# M900dec.net
KiCad netlist of a schematic drawn in EAGLE
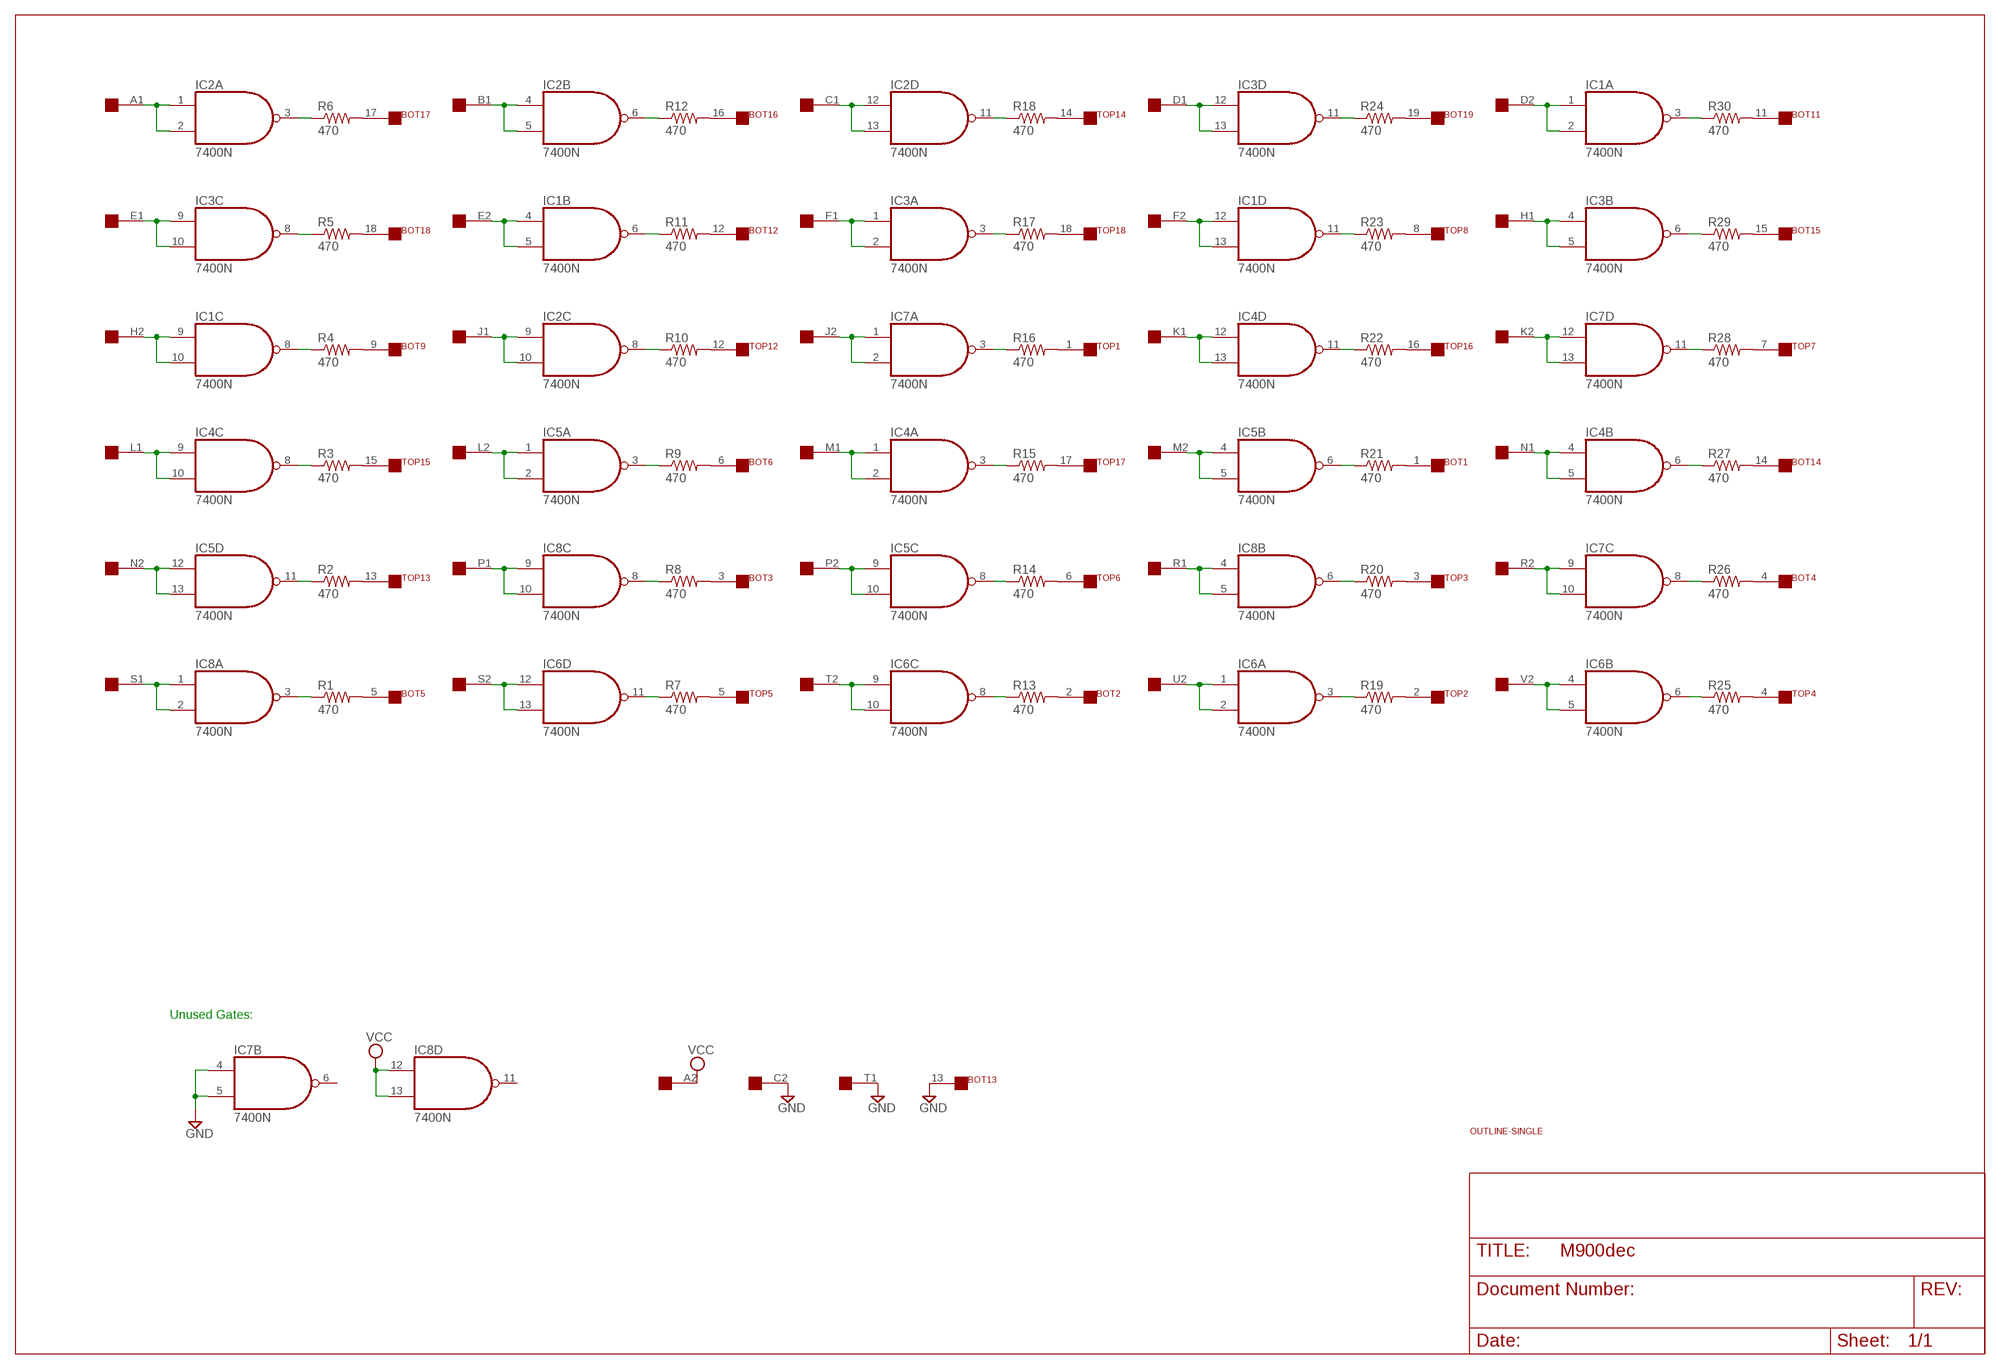
[diagram p0: schematic, sheet 1]

(export (version "E")
  (design (tool "Eeschema 10.0.6"))
  (components
    (comp (ref "BOT")
      (value "FLEX19")
      (footprint "eagle-import:FLEX19")
      (libsource (lib "eagle-import") (part "FLEX19"))
    )
    (comp (ref "EDGE")
      (value "SINGLE")
      (footprint "eagle-import:EDGE-CON2")
      (libsource (lib "eagle-import") (part "SINGLE"))
    )
    (comp (ref "IC1")
      (value "7400N")
      (footprint "eagle-import:DIL14")
      (libsource (lib "eagle-import") (part "7400N"))
    )
    (comp (ref "IC2")
      (value "7400N")
      (footprint "eagle-import:DIL14")
      (libsource (lib "eagle-import") (part "7400N"))
    )
    (comp (ref "IC3")
      (value "7400N")
      (footprint "eagle-import:DIL14")
      (libsource (lib "eagle-import") (part "7400N"))
    )
    (comp (ref "IC4")
      (value "7400N")
      (footprint "eagle-import:DIL14")
      (libsource (lib "eagle-import") (part "7400N"))
    )
    (comp (ref "IC5")
      (value "7400N")
      (footprint "eagle-import:DIL14")
      (libsource (lib "eagle-import") (part "7400N"))
    )
    (comp (ref "IC6")
      (value "7400N")
      (footprint "eagle-import:DIL14")
      (libsource (lib "eagle-import") (part "7400N"))
    )
    (comp (ref "IC7")
      (value "7400N")
      (footprint "eagle-import:DIL14")
      (libsource (lib "eagle-import") (part "7400N"))
    )
    (comp (ref "IC8")
      (value "7400N")
      (footprint "eagle-import:DIL14")
      (libsource (lib "eagle-import") (part "7400N"))
    )
    (comp (ref "R1")
      (value "470")
      (footprint "eagle-import:0207_10")
      (libsource (lib "eagle-import") (part "R-US_0207/10"))
    )
    (comp (ref "R2")
      (value "470")
      (footprint "eagle-import:0207_10")
      (libsource (lib "eagle-import") (part "R-US_0207/10"))
    )
    (comp (ref "R3")
      (value "470")
      (footprint "eagle-import:0207_10")
      (libsource (lib "eagle-import") (part "R-US_0207/10"))
    )
    (comp (ref "R4")
      (value "470")
      (footprint "eagle-import:0207_10")
      (libsource (lib "eagle-import") (part "R-US_0207/10"))
    )
    (comp (ref "R5")
      (value "470")
      (footprint "eagle-import:0207_10")
      (libsource (lib "eagle-import") (part "R-US_0207/10"))
    )
    (comp (ref "R6")
      (value "470")
      (footprint "eagle-import:0207_10")
      (libsource (lib "eagle-import") (part "R-US_0207/10"))
    )
    (comp (ref "R7")
      (value "470")
      (footprint "eagle-import:0207_10")
      (libsource (lib "eagle-import") (part "R-US_0207/10"))
    )
    (comp (ref "R8")
      (value "470")
      (footprint "eagle-import:0207_10")
      (libsource (lib "eagle-import") (part "R-US_0207/10"))
    )
    (comp (ref "R9")
      (value "470")
      (footprint "eagle-import:0207_10")
      (libsource (lib "eagle-import") (part "R-US_0207/10"))
    )
    (comp (ref "R10")
      (value "470")
      (footprint "eagle-import:0207_10")
      (libsource (lib "eagle-import") (part "R-US_0207/10"))
    )
    (comp (ref "R11")
      (value "470")
      (footprint "eagle-import:0207_10")
      (libsource (lib "eagle-import") (part "R-US_0207/10"))
    )
    (comp (ref "R12")
      (value "470")
      (footprint "eagle-import:0207_10")
      (libsource (lib "eagle-import") (part "R-US_0207/10"))
    )
    (comp (ref "R13")
      (value "470")
      (footprint "eagle-import:0207_10")
      (libsource (lib "eagle-import") (part "R-US_0207/10"))
    )
    (comp (ref "R14")
      (value "470")
      (footprint "eagle-import:0207_10")
      (libsource (lib "eagle-import") (part "R-US_0207/10"))
    )
    (comp (ref "R15")
      (value "470")
      (footprint "eagle-import:0207_10")
      (libsource (lib "eagle-import") (part "R-US_0207/10"))
    )
    (comp (ref "R16")
      (value "470")
      (footprint "eagle-import:0207_10")
      (libsource (lib "eagle-import") (part "R-US_0207/10"))
    )
    (comp (ref "R17")
      (value "470")
      (footprint "eagle-import:0207_10")
      (libsource (lib "eagle-import") (part "R-US_0207/10"))
    )
    (comp (ref "R18")
      (value "470")
      (footprint "eagle-import:0207_10")
      (libsource (lib "eagle-import") (part "R-US_0207/10"))
    )
    (comp (ref "R19")
      (value "470")
      (footprint "eagle-import:0207_10")
      (libsource (lib "eagle-import") (part "R-US_0207/10"))
    )
    (comp (ref "R20")
      (value "470")
      (footprint "eagle-import:0207_10")
      (libsource (lib "eagle-import") (part "R-US_0207/10"))
    )
    (comp (ref "R21")
      (value "470")
      (footprint "eagle-import:0207_10")
      (libsource (lib "eagle-import") (part "R-US_0207/10"))
    )
    (comp (ref "R22")
      (value "470")
      (footprint "eagle-import:0207_10")
      (libsource (lib "eagle-import") (part "R-US_0207/10"))
    )
    (comp (ref "R23")
      (value "470")
      (footprint "eagle-import:0207_10")
      (libsource (lib "eagle-import") (part "R-US_0207/10"))
    )
    (comp (ref "R24")
      (value "470")
      (footprint "eagle-import:0207_10")
      (libsource (lib "eagle-import") (part "R-US_0207/10"))
    )
    (comp (ref "R25")
      (value "470")
      (footprint "eagle-import:0207_10")
      (libsource (lib "eagle-import") (part "R-US_0207/10"))
    )
    (comp (ref "R26")
      (value "470")
      (footprint "eagle-import:0207_10")
      (libsource (lib "eagle-import") (part "R-US_0207/10"))
    )
    (comp (ref "R27")
      (value "470")
      (footprint "eagle-import:0207_10")
      (libsource (lib "eagle-import") (part "R-US_0207/10"))
    )
    (comp (ref "R28")
      (value "470")
      (footprint "eagle-import:0207_10")
      (libsource (lib "eagle-import") (part "R-US_0207/10"))
    )
    (comp (ref "R29")
      (value "470")
      (footprint "eagle-import:0207_10")
      (libsource (lib "eagle-import") (part "R-US_0207/10"))
    )
    (comp (ref "R30")
      (value "470")
      (footprint "eagle-import:0207_10")
      (libsource (lib "eagle-import") (part "R-US_0207/10"))
    )
    (comp (ref "TOP")
      (value "FLEX19")
      (footprint "eagle-import:FLEX19")
      (libsource (lib "eagle-import") (part "FLEX19"))
    )
    (comp (ref "U$2")
      (value "OUTLINE-SINGLE")
      (footprint "eagle-import:SINGLE")
      (libsource (lib "eagle-import") (part "OUTLINE-SINGLE"))
    )
  )
  (nets
    (net (code "1") (name "GND") (class "Default")
      (node (ref "BOT") (pin "13") (pinfunction "1_13") (pintype "passive"))
      (node (ref "EDGE") (pin "C2") (pinfunction "1_C2") (pintype "bidirectional"))
      (node (ref "EDGE") (pin "T1") (pinfunction "1_T1") (pintype "bidirectional"))
      (node (ref "IC7") (pin "4") (pinfunction "I0_4") (pintype "input"))
      (node (ref "IC7") (pin "5") (pinfunction "I1_5") (pintype "input"))
    )
    (net (code "2") (name "Net-(BOT-Pad1)") (class "Default")
      (node (ref "BOT") (pin "1") (pinfunction "1_1") (pintype "passive"))
      (node (ref "R21") (pin "2") (pinfunction "2_2") (pintype "passive"))
    )
    (net (code "3") (name "Net-(BOTC-1)") (class "Default")
      (node (ref "BOT") (pin "11") (pinfunction "1_11") (pintype "passive"))
      (node (ref "R30") (pin "2") (pinfunction "2_2") (pintype "passive"))
    )
    (net (code "4") (name "Net-(BOTD-1)") (class "Default")
      (node (ref "BOT") (pin "12") (pinfunction "1_12") (pintype "passive"))
      (node (ref "R11") (pin "2") (pinfunction "2_2") (pintype "passive"))
    )
    (net (code "5") (name "Net-(BOTF-1)") (class "Default")
      (node (ref "BOT") (pin "14") (pinfunction "1_14") (pintype "passive"))
      (node (ref "R27") (pin "2") (pinfunction "2_2") (pintype "passive"))
    )
    (net (code "6") (name "Net-(BOTG-1)") (class "Default")
      (node (ref "BOT") (pin "15") (pinfunction "1_15") (pintype "passive"))
      (node (ref "R29") (pin "2") (pinfunction "2_2") (pintype "passive"))
    )
    (net (code "7") (name "Net-(BOTH-1)") (class "Default")
      (node (ref "BOT") (pin "16") (pinfunction "1_16") (pintype "passive"))
      (node (ref "R12") (pin "2") (pinfunction "2_2") (pintype "passive"))
    )
    (net (code "8") (name "Net-(BOTI-1)") (class "Default")
      (node (ref "BOT") (pin "17") (pinfunction "1_17") (pintype "passive"))
      (node (ref "R6") (pin "2") (pinfunction "2_2") (pintype "passive"))
    )
    (net (code "9") (name "Net-(BOTJ-1)") (class "Default")
      (node (ref "BOT") (pin "18") (pinfunction "1_18") (pintype "passive"))
      (node (ref "R5") (pin "2") (pinfunction "2_2") (pintype "passive"))
    )
    (net (code "10") (name "Net-(BOTK-1)") (class "Default")
      (node (ref "BOT") (pin "19") (pinfunction "1_19") (pintype "passive"))
      (node (ref "R24") (pin "2") (pinfunction "2_2") (pintype "passive"))
    )
    (net (code "11") (name "Net-(BOTL-1)") (class "Default")
      (node (ref "BOT") (pin "2") (pinfunction "1_2") (pintype "passive"))
      (node (ref "R13") (pin "2") (pinfunction "2_2") (pintype "passive"))
    )
    (net (code "12") (name "Net-(BOTM-1)") (class "Default")
      (node (ref "BOT") (pin "3") (pinfunction "1_3") (pintype "passive"))
      (node (ref "R8") (pin "2") (pinfunction "2_2") (pintype "passive"))
    )
    (net (code "13") (name "Net-(BOTN-1)") (class "Default")
      (node (ref "BOT") (pin "4") (pinfunction "1_4") (pintype "passive"))
      (node (ref "R26") (pin "2") (pinfunction "2_2") (pintype "passive"))
    )
    (net (code "14") (name "Net-(BOTO-1)") (class "Default")
      (node (ref "BOT") (pin "5") (pinfunction "1_5") (pintype "passive"))
      (node (ref "R1") (pin "2") (pinfunction "2_2") (pintype "passive"))
    )
    (net (code "15") (name "Net-(BOTP-1)") (class "Default")
      (node (ref "BOT") (pin "6") (pinfunction "1_6") (pintype "passive"))
      (node (ref "R9") (pin "2") (pinfunction "2_2") (pintype "passive"))
    )
    (net (code "16") (name "Net-(BOTS-1)") (class "Default")
      (node (ref "BOT") (pin "9") (pinfunction "1_9") (pintype "passive"))
      (node (ref "R4") (pin "2") (pinfunction "2_2") (pintype "passive"))
    )
    (net (code "17") (name "Net-(EDGEA-1)") (class "Default")
      (node (ref "EDGE") (pin "A1") (pinfunction "1_A1") (pintype "bidirectional"))
      (node (ref "IC2") (pin "1") (pinfunction "I0_1") (pintype "input"))
      (node (ref "IC2") (pin "2") (pinfunction "I1_2") (pintype "input"))
    )
    (net (code "18") (name "Net-(EDGEAA-1)") (class "Default")
      (node (ref "EDGE") (pin "R1") (pinfunction "1_R1") (pintype "bidirectional"))
      (node (ref "IC8") (pin "4") (pinfunction "I0_4") (pintype "input"))
      (node (ref "IC8") (pin "5") (pinfunction "I1_5") (pintype "input"))
    )
    (net (code "19") (name "Net-(EDGEAB-1)") (class "Default")
      (node (ref "EDGE") (pin "R2") (pinfunction "1_R2") (pintype "bidirectional"))
      (node (ref "IC7") (pin "10") (pinfunction "I1_10") (pintype "input"))
      (node (ref "IC7") (pin "9") (pinfunction "I0_9") (pintype "input"))
    )
    (net (code "20") (name "Net-(EDGEAC-1)") (class "Default")
      (node (ref "EDGE") (pin "S1") (pinfunction "1_S1") (pintype "bidirectional"))
      (node (ref "IC8") (pin "1") (pinfunction "I0_1") (pintype "input"))
      (node (ref "IC8") (pin "2") (pinfunction "I1_2") (pintype "input"))
    )
    (net (code "21") (name "Net-(EDGEAD-1)") (class "Default")
      (node (ref "EDGE") (pin "S2") (pinfunction "1_S2") (pintype "bidirectional"))
      (node (ref "IC6") (pin "12") (pinfunction "I0_12") (pintype "input"))
      (node (ref "IC6") (pin "13") (pinfunction "I1_13") (pintype "input"))
    )
    (net (code "22") (name "Net-(EDGEAF-1)") (class "Default")
      (node (ref "EDGE") (pin "T2") (pinfunction "1_T2") (pintype "bidirectional"))
      (node (ref "IC6") (pin "10") (pinfunction "I1_10") (pintype "input"))
      (node (ref "IC6") (pin "9") (pinfunction "I0_9") (pintype "input"))
    )
    (net (code "23") (name "Net-(EDGEAH-1)") (class "Default")
      (node (ref "EDGE") (pin "U2") (pinfunction "1_U2") (pintype "bidirectional"))
      (node (ref "IC6") (pin "1") (pinfunction "I0_1") (pintype "input"))
      (node (ref "IC6") (pin "2") (pinfunction "I1_2") (pintype "input"))
    )
    (net (code "24") (name "Net-(EDGEAJ-1)") (class "Default")
      (node (ref "EDGE") (pin "V2") (pinfunction "1_V2") (pintype "bidirectional"))
      (node (ref "IC6") (pin "4") (pinfunction "I0_4") (pintype "input"))
      (node (ref "IC6") (pin "5") (pinfunction "I1_5") (pintype "input"))
    )
    (net (code "25") (name "Net-(EDGEC-1)") (class "Default")
      (node (ref "EDGE") (pin "B1") (pinfunction "1_B1") (pintype "bidirectional"))
      (node (ref "IC2") (pin "4") (pinfunction "I0_4") (pintype "input"))
      (node (ref "IC2") (pin "5") (pinfunction "I1_5") (pintype "input"))
    )
    (net (code "26") (name "Net-(EDGEE-1)") (class "Default")
      (node (ref "EDGE") (pin "C1") (pinfunction "1_C1") (pintype "bidirectional"))
      (node (ref "IC2") (pin "12") (pinfunction "I0_12") (pintype "input"))
      (node (ref "IC2") (pin "13") (pinfunction "I1_13") (pintype "input"))
    )
    (net (code "27") (name "Net-(EDGEG-1)") (class "Default")
      (node (ref "EDGE") (pin "D1") (pinfunction "1_D1") (pintype "bidirectional"))
      (node (ref "IC3") (pin "12") (pinfunction "I0_12") (pintype "input"))
      (node (ref "IC3") (pin "13") (pinfunction "I1_13") (pintype "input"))
    )
    (net (code "28") (name "Net-(EDGEH-1)") (class "Default")
      (node (ref "EDGE") (pin "D2") (pinfunction "1_D2") (pintype "bidirectional"))
      (node (ref "IC1") (pin "1") (pinfunction "I0_1") (pintype "input"))
      (node (ref "IC1") (pin "2") (pinfunction "I1_2") (pintype "input"))
    )
    (net (code "29") (name "Net-(EDGEI-1)") (class "Default")
      (node (ref "EDGE") (pin "E1") (pinfunction "1_E1") (pintype "bidirectional"))
      (node (ref "IC3") (pin "10") (pinfunction "I1_10") (pintype "input"))
      (node (ref "IC3") (pin "9") (pinfunction "I0_9") (pintype "input"))
    )
    (net (code "30") (name "Net-(EDGEJ-1)") (class "Default")
      (node (ref "EDGE") (pin "E2") (pinfunction "1_E2") (pintype "bidirectional"))
      (node (ref "IC1") (pin "4") (pinfunction "I0_4") (pintype "input"))
      (node (ref "IC1") (pin "5") (pinfunction "I1_5") (pintype "input"))
    )
    (net (code "31") (name "Net-(EDGEK-1)") (class "Default")
      (node (ref "EDGE") (pin "F1") (pinfunction "1_F1") (pintype "bidirectional"))
      (node (ref "IC3") (pin "1") (pinfunction "I0_1") (pintype "input"))
      (node (ref "IC3") (pin "2") (pinfunction "I1_2") (pintype "input"))
    )
    (net (code "32") (name "Net-(EDGEL-1)") (class "Default")
      (node (ref "EDGE") (pin "F2") (pinfunction "1_F2") (pintype "bidirectional"))
      (node (ref "IC1") (pin "12") (pinfunction "I0_12") (pintype "input"))
      (node (ref "IC1") (pin "13") (pinfunction "I1_13") (pintype "input"))
    )
    (net (code "33") (name "Net-(EDGEM-1)") (class "Default")
      (node (ref "EDGE") (pin "H1") (pinfunction "1_H1") (pintype "bidirectional"))
      (node (ref "IC3") (pin "4") (pinfunction "I0_4") (pintype "input"))
      (node (ref "IC3") (pin "5") (pinfunction "I1_5") (pintype "input"))
    )
    (net (code "34") (name "Net-(EDGEN-1)") (class "Default")
      (node (ref "EDGE") (pin "H2") (pinfunction "1_H2") (pintype "bidirectional"))
      (node (ref "IC1") (pin "10") (pinfunction "I1_10") (pintype "input"))
      (node (ref "IC1") (pin "9") (pinfunction "I0_9") (pintype "input"))
    )
    (net (code "35") (name "Net-(EDGEO-1)") (class "Default")
      (node (ref "EDGE") (pin "J1") (pinfunction "1_J1") (pintype "bidirectional"))
      (node (ref "IC2") (pin "10") (pinfunction "I1_10") (pintype "input"))
      (node (ref "IC2") (pin "9") (pinfunction "I0_9") (pintype "input"))
    )
    (net (code "36") (name "Net-(EDGEP-1)") (class "Default")
      (node (ref "EDGE") (pin "J2") (pinfunction "1_J2") (pintype "bidirectional"))
      (node (ref "IC7") (pin "1") (pinfunction "I0_1") (pintype "input"))
      (node (ref "IC7") (pin "2") (pinfunction "I1_2") (pintype "input"))
    )
    (net (code "37") (name "Net-(EDGEQ-1)") (class "Default")
      (node (ref "EDGE") (pin "K1") (pinfunction "1_K1") (pintype "bidirectional"))
      (node (ref "IC4") (pin "12") (pinfunction "I0_12") (pintype "input"))
      (node (ref "IC4") (pin "13") (pinfunction "I1_13") (pintype "input"))
    )
    (net (code "38") (name "Net-(EDGER-1)") (class "Default")
      (node (ref "EDGE") (pin "K2") (pinfunction "1_K2") (pintype "bidirectional"))
      (node (ref "IC7") (pin "12") (pinfunction "I0_12") (pintype "input"))
      (node (ref "IC7") (pin "13") (pinfunction "I1_13") (pintype "input"))
    )
    (net (code "39") (name "Net-(EDGES-1)") (class "Default")
      (node (ref "EDGE") (pin "L1") (pinfunction "1_L1") (pintype "bidirectional"))
      (node (ref "IC4") (pin "10") (pinfunction "I1_10") (pintype "input"))
      (node (ref "IC4") (pin "9") (pinfunction "I0_9") (pintype "input"))
    )
    (net (code "40") (name "Net-(EDGET-1)") (class "Default")
      (node (ref "EDGE") (pin "L2") (pinfunction "1_L2") (pintype "bidirectional"))
      (node (ref "IC5") (pin "1") (pinfunction "I0_1") (pintype "input"))
      (node (ref "IC5") (pin "2") (pinfunction "I1_2") (pintype "input"))
    )
    (net (code "41") (name "Net-(EDGEU-1)") (class "Default")
      (node (ref "EDGE") (pin "M1") (pinfunction "1_M1") (pintype "bidirectional"))
      (node (ref "IC4") (pin "1") (pinfunction "I0_1") (pintype "input"))
      (node (ref "IC4") (pin "2") (pinfunction "I1_2") (pintype "input"))
    )
    (net (code "42") (name "Net-(EDGEV-1)") (class "Default")
      (node (ref "EDGE") (pin "M2") (pinfunction "1_M2") (pintype "bidirectional"))
      (node (ref "IC5") (pin "4") (pinfunction "I0_4") (pintype "input"))
      (node (ref "IC5") (pin "5") (pinfunction "I1_5") (pintype "input"))
    )
    (net (code "43") (name "Net-(EDGEW-1)") (class "Default")
      (node (ref "EDGE") (pin "N1") (pinfunction "1_N1") (pintype "bidirectional"))
      (node (ref "IC4") (pin "4") (pinfunction "I0_4") (pintype "input"))
      (node (ref "IC4") (pin "5") (pinfunction "I1_5") (pintype "input"))
    )
    (net (code "44") (name "Net-(EDGEX-1)") (class "Default")
      (node (ref "EDGE") (pin "N2") (pinfunction "1_N2") (pintype "bidirectional"))
      (node (ref "IC5") (pin "12") (pinfunction "I0_12") (pintype "input"))
      (node (ref "IC5") (pin "13") (pinfunction "I1_13") (pintype "input"))
    )
    (net (code "45") (name "Net-(EDGEY-1)") (class "Default")
      (node (ref "EDGE") (pin "P1") (pinfunction "1_P1") (pintype "bidirectional"))
      (node (ref "IC8") (pin "10") (pinfunction "I1_10") (pintype "input"))
      (node (ref "IC8") (pin "9") (pinfunction "I0_9") (pintype "input"))
    )
    (net (code "46") (name "Net-(EDGEZ-1)") (class "Default")
      (node (ref "EDGE") (pin "P2") (pinfunction "1_P2") (pintype "bidirectional"))
      (node (ref "IC5") (pin "10") (pinfunction "I1_10") (pintype "input"))
      (node (ref "IC5") (pin "9") (pinfunction "I0_9") (pintype "input"))
    )
    (net (code "47") (name "Net-(IC1A-O)") (class "Default")
      (node (ref "IC1") (pin "3") (pinfunction "O_3") (pintype "output"))
      (node (ref "R30") (pin "1") (pinfunction "1_1") (pintype "passive"))
    )
    (net (code "48") (name "Net-(IC1B-O)") (class "Default")
      (node (ref "IC1") (pin "6") (pinfunction "O_6") (pintype "output"))
      (node (ref "R11") (pin "1") (pinfunction "1_1") (pintype "passive"))
    )
    (net (code "49") (name "Net-(IC1C-O)") (class "Default")
      (node (ref "IC1") (pin "8") (pinfunction "O_8") (pintype "output"))
      (node (ref "R4") (pin "1") (pinfunction "1_1") (pintype "passive"))
    )
    (net (code "50") (name "Net-(IC1D-O)") (class "Default")
      (node (ref "IC1") (pin "11") (pinfunction "O_11") (pintype "output"))
      (node (ref "R23") (pin "1") (pinfunction "1_1") (pintype "passive"))
    )
    (net (code "51") (name "Net-(IC2A-O)") (class "Default")
      (node (ref "IC2") (pin "3") (pinfunction "O_3") (pintype "output"))
      (node (ref "R6") (pin "1") (pinfunction "1_1") (pintype "passive"))
    )
    (net (code "52") (name "Net-(IC2B-O)") (class "Default")
      (node (ref "IC2") (pin "6") (pinfunction "O_6") (pintype "output"))
      (node (ref "R12") (pin "1") (pinfunction "1_1") (pintype "passive"))
    )
    (net (code "53") (name "Net-(IC2C-O)") (class "Default")
      (node (ref "IC2") (pin "8") (pinfunction "O_8") (pintype "output"))
      (node (ref "R10") (pin "1") (pinfunction "1_1") (pintype "passive"))
    )
    (net (code "54") (name "Net-(IC2D-O)") (class "Default")
      (node (ref "IC2") (pin "11") (pinfunction "O_11") (pintype "output"))
      (node (ref "R18") (pin "1") (pinfunction "1_1") (pintype "passive"))
    )
    (net (code "55") (name "Net-(IC3A-O)") (class "Default")
      (node (ref "IC3") (pin "3") (pinfunction "O_3") (pintype "output"))
      (node (ref "R17") (pin "1") (pinfunction "1_1") (pintype "passive"))
    )
    (net (code "56") (name "Net-(IC3B-O)") (class "Default")
      (node (ref "IC3") (pin "6") (pinfunction "O_6") (pintype "output"))
      (node (ref "R29") (pin "1") (pinfunction "1_1") (pintype "passive"))
    )
    (net (code "57") (name "Net-(IC3C-O)") (class "Default")
      (node (ref "IC3") (pin "8") (pinfunction "O_8") (pintype "output"))
      (node (ref "R5") (pin "1") (pinfunction "1_1") (pintype "passive"))
    )
    (net (code "58") (name "Net-(IC3D-O)") (class "Default")
      (node (ref "IC3") (pin "11") (pinfunction "O_11") (pintype "output"))
      (node (ref "R24") (pin "1") (pinfunction "1_1") (pintype "passive"))
    )
    (net (code "59") (name "Net-(IC4A-O)") (class "Default")
      (node (ref "IC4") (pin "3") (pinfunction "O_3") (pintype "output"))
      (node (ref "R15") (pin "1") (pinfunction "1_1") (pintype "passive"))
    )
    (net (code "60") (name "Net-(IC4B-O)") (class "Default")
      (node (ref "IC4") (pin "6") (pinfunction "O_6") (pintype "output"))
      (node (ref "R27") (pin "1") (pinfunction "1_1") (pintype "passive"))
    )
    (net (code "61") (name "Net-(IC4C-O)") (class "Default")
      (node (ref "IC4") (pin "8") (pinfunction "O_8") (pintype "output"))
      (node (ref "R3") (pin "1") (pinfunction "1_1") (pintype "passive"))
    )
    (net (code "62") (name "Net-(IC4D-O)") (class "Default")
      (node (ref "IC4") (pin "11") (pinfunction "O_11") (pintype "output"))
      (node (ref "R22") (pin "1") (pinfunction "1_1") (pintype "passive"))
    )
    (net (code "63") (name "Net-(IC5A-O)") (class "Default")
      (node (ref "IC5") (pin "3") (pinfunction "O_3") (pintype "output"))
      (node (ref "R9") (pin "1") (pinfunction "1_1") (pintype "passive"))
    )
    (net (code "64") (name "Net-(IC5B-O)") (class "Default")
      (node (ref "IC5") (pin "6") (pinfunction "O_6") (pintype "output"))
      (node (ref "R21") (pin "1") (pinfunction "1_1") (pintype "passive"))
    )
    (net (code "65") (name "Net-(IC5C-O)") (class "Default")
      (node (ref "IC5") (pin "8") (pinfunction "O_8") (pintype "output"))
      (node (ref "R14") (pin "1") (pinfunction "1_1") (pintype "passive"))
    )
    (net (code "66") (name "Net-(IC5D-O)") (class "Default")
      (node (ref "IC5") (pin "11") (pinfunction "O_11") (pintype "output"))
      (node (ref "R2") (pin "1") (pinfunction "1_1") (pintype "passive"))
    )
    (net (code "67") (name "Net-(IC6A-O)") (class "Default")
      (node (ref "IC6") (pin "3") (pinfunction "O_3") (pintype "output"))
      (node (ref "R19") (pin "1") (pinfunction "1_1") (pintype "passive"))
    )
    (net (code "68") (name "Net-(IC6B-O)") (class "Default")
      (node (ref "IC6") (pin "6") (pinfunction "O_6") (pintype "output"))
      (node (ref "R25") (pin "1") (pinfunction "1_1") (pintype "passive"))
    )
    (net (code "69") (name "Net-(IC6C-O)") (class "Default")
      (node (ref "IC6") (pin "8") (pinfunction "O_8") (pintype "output"))
      (node (ref "R13") (pin "1") (pinfunction "1_1") (pintype "passive"))
    )
    (net (code "70") (name "Net-(IC6D-O)") (class "Default")
      (node (ref "IC6") (pin "11") (pinfunction "O_11") (pintype "output"))
      (node (ref "R7") (pin "1") (pinfunction "1_1") (pintype "passive"))
    )
    (net (code "71") (name "Net-(IC7A-O)") (class "Default")
      (node (ref "IC7") (pin "3") (pinfunction "O_3") (pintype "output"))
      (node (ref "R16") (pin "1") (pinfunction "1_1") (pintype "passive"))
    )
    (net (code "72") (name "Net-(IC7C-O)") (class "Default")
      (node (ref "IC7") (pin "8") (pinfunction "O_8") (pintype "output"))
      (node (ref "R26") (pin "1") (pinfunction "1_1") (pintype "passive"))
    )
    (net (code "73") (name "Net-(IC7D-O)") (class "Default")
      (node (ref "IC7") (pin "11") (pinfunction "O_11") (pintype "output"))
      (node (ref "R28") (pin "1") (pinfunction "1_1") (pintype "passive"))
    )
    (net (code "74") (name "Net-(IC8A-O)") (class "Default")
      (node (ref "IC8") (pin "3") (pinfunction "O_3") (pintype "output"))
      (node (ref "R1") (pin "1") (pinfunction "1_1") (pintype "passive"))
    )
    (net (code "75") (name "Net-(IC8B-O)") (class "Default")
      (node (ref "IC8") (pin "6") (pinfunction "O_6") (pintype "output"))
      (node (ref "R20") (pin "1") (pinfunction "1_1") (pintype "passive"))
    )
    (net (code "76") (name "Net-(IC8C-O)") (class "Default")
      (node (ref "IC8") (pin "8") (pinfunction "O_8") (pintype "output"))
      (node (ref "R8") (pin "1") (pinfunction "1_1") (pintype "passive"))
    )
    (net (code "77") (name "Net-(R16-Pad2)") (class "Default")
      (node (ref "R16") (pin "2") (pinfunction "2_2") (pintype "passive"))
      (node (ref "TOP") (pin "1") (pinfunction "1_1") (pintype "passive"))
    )
    (net (code "78") (name "Net-(TOPD-1)") (class "Default")
      (node (ref "R10") (pin "2") (pinfunction "2_2") (pintype "passive"))
      (node (ref "TOP") (pin "12") (pinfunction "1_12") (pintype "passive"))
    )
    (net (code "79") (name "Net-(TOPE-1)") (class "Default")
      (node (ref "R2") (pin "2") (pinfunction "2_2") (pintype "passive"))
      (node (ref "TOP") (pin "13") (pinfunction "1_13") (pintype "passive"))
    )
    (net (code "80") (name "Net-(TOPF-1)") (class "Default")
      (node (ref "R18") (pin "2") (pinfunction "2_2") (pintype "passive"))
      (node (ref "TOP") (pin "14") (pinfunction "1_14") (pintype "passive"))
    )
    (net (code "81") (name "Net-(TOPG-1)") (class "Default")
      (node (ref "R3") (pin "2") (pinfunction "2_2") (pintype "passive"))
      (node (ref "TOP") (pin "15") (pinfunction "1_15") (pintype "passive"))
    )
    (net (code "82") (name "Net-(TOPH-1)") (class "Default")
      (node (ref "R22") (pin "2") (pinfunction "2_2") (pintype "passive"))
      (node (ref "TOP") (pin "16") (pinfunction "1_16") (pintype "passive"))
    )
    (net (code "83") (name "Net-(TOPI-1)") (class "Default")
      (node (ref "R15") (pin "2") (pinfunction "2_2") (pintype "passive"))
      (node (ref "TOP") (pin "17") (pinfunction "1_17") (pintype "passive"))
    )
    (net (code "84") (name "Net-(TOPJ-1)") (class "Default")
      (node (ref "R17") (pin "2") (pinfunction "2_2") (pintype "passive"))
      (node (ref "TOP") (pin "18") (pinfunction "1_18") (pintype "passive"))
    )
    (net (code "85") (name "Net-(TOPL-1)") (class "Default")
      (node (ref "R19") (pin "2") (pinfunction "2_2") (pintype "passive"))
      (node (ref "TOP") (pin "2") (pinfunction "1_2") (pintype "passive"))
    )
    (net (code "86") (name "Net-(TOPM-1)") (class "Default")
      (node (ref "R20") (pin "2") (pinfunction "2_2") (pintype "passive"))
      (node (ref "TOP") (pin "3") (pinfunction "1_3") (pintype "passive"))
    )
    (net (code "87") (name "Net-(TOPN-1)") (class "Default")
      (node (ref "R25") (pin "2") (pinfunction "2_2") (pintype "passive"))
      (node (ref "TOP") (pin "4") (pinfunction "1_4") (pintype "passive"))
    )
    (net (code "88") (name "Net-(TOPO-1)") (class "Default")
      (node (ref "R7") (pin "2") (pinfunction "2_2") (pintype "passive"))
      (node (ref "TOP") (pin "5") (pinfunction "1_5") (pintype "passive"))
    )
    (net (code "89") (name "Net-(TOPP-1)") (class "Default")
      (node (ref "R14") (pin "2") (pinfunction "2_2") (pintype "passive"))
      (node (ref "TOP") (pin "6") (pinfunction "1_6") (pintype "passive"))
    )
    (net (code "90") (name "Net-(TOPQ-1)") (class "Default")
      (node (ref "R28") (pin "2") (pinfunction "2_2") (pintype "passive"))
      (node (ref "TOP") (pin "7") (pinfunction "1_7") (pintype "passive"))
    )
    (net (code "91") (name "Net-(TOPR-1)") (class "Default")
      (node (ref "R23") (pin "2") (pinfunction "2_2") (pintype "passive"))
      (node (ref "TOP") (pin "8") (pinfunction "1_8") (pintype "passive"))
    )
    (net (code "92") (name "VCC") (class "Default")
      (node (ref "EDGE") (pin "A2") (pinfunction "1_A2") (pintype "bidirectional"))
      (node (ref "IC8") (pin "12") (pinfunction "I0_12") (pintype "input"))
      (node (ref "IC8") (pin "13") (pinfunction "I1_13") (pintype "input"))
    )
    (net (code "93") (name "unconnected-(IC7B-O-Pad6)") (class "Default")
      (node (ref "IC7") (pin "6") (pinfunction "O_6") (pintype "output"))
    )
    (net (code "94") (name "unconnected-(IC8D-O-Pad11)") (class "Default")
      (node (ref "IC8") (pin "11") (pinfunction "O_11") (pintype "output"))
    )
  )
)
